# Sheet2.net
KiCad netlist of a schematic drawn in Altium Designer
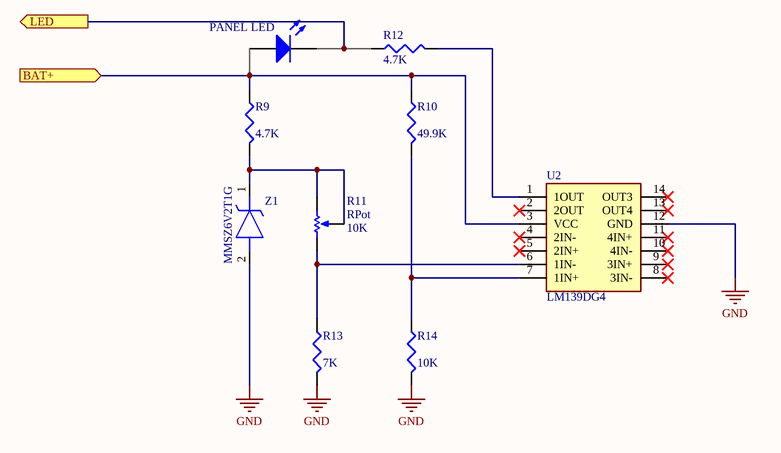
[diagram p0: Sheet2.SchDoc]

(export (version "E")
  (design (tool "Eeschema 10.0.6"))
  (components
    (comp (ref "D5")
      (value "PANEL LED")
      (footprint "LED-1")
      (description "Typical BLUE SiC LED")
      (fields (field (name "PUBLISHER") "Altium Limited"))
      (libsource (lib "Miscellaneous Devices") (part "LED3"))
    )
    (comp (ref "R9")
      (value "4.7K")
      (footprint "RESC1608X55N")
      (description "Resistor")
      (fields (field (name "Comment") "Res3") (field (name "PUBLISHER") "Altium Limited"))
      (libsource (lib "Miscellaneous Devices") (part "Res3"))
    )
    (comp (ref "R10")
      (value "49.9K")
      (footprint "RESC1608X55N")
      (description "Resistor")
      (fields (field (name "Comment") "Res3") (field (name "PUBLISHER") "Altium Limited"))
      (libsource (lib "Miscellaneous Devices") (part "Res3"))
    )
    (comp (ref "R11")
      (value "RPot")
      (footprint "Bourns_Pot")
      (description "Potentiometer")
      (fields (field (name "ALTIUM_VALUE") "10K") (field (name "PUBLISHER") "Altium Limited"))
      (libsource (lib "Miscellaneous Devices") (part "RPot"))
    )
    (comp (ref "R12")
      (value "4.7K")
      (footprint "RESC1608X55N")
      (description "Resistor")
      (fields (field (name "Comment") "Res3") (field (name "PUBLISHER") "Altium Limited"))
      (libsource (lib "Miscellaneous Devices") (part "Res3"))
    )
    (comp (ref "R13")
      (value "7K")
      (footprint "RESC1608X55N")
      (description "Resistor")
      (fields (field (name "Comment") "Res3") (field (name "PUBLISHER") "Altium Limited"))
      (libsource (lib "Miscellaneous Devices") (part "Res3"))
    )
    (comp (ref "R14")
      (value "10K")
      (footprint "RESC1608X55N")
      (description "Resistor")
      (fields (field (name "Comment") "Res3") (field (name "PUBLISHER") "Altium Limited"))
      (libsource (lib "Miscellaneous Devices") (part "Res3"))
    )
    (comp (ref "U2")
      (value "LM139DG4")
      (footprint "SamacSys:SOIC127P600X175-14N")
      (description "Integrated Circuit")
      (fields (field (name "MOUSER PART NUMBER") "595-LM139DG4"))
      (libsource (lib "*") (part "LM139DG4"))
    )
    (comp (ref "Z1")
      (value "MMSZ6V2T1G")
      (footprint "SamacSys:SOD3716X135N")
      (description "Zener Diode")
      (fields (field (name "MOUSER PART NUMBER") "863-MMSZ6V2T1G"))
      (libsource (lib "*") (part "MMSZ6V2T1G"))
    )
  )
  (nets
    (net (code "1") (name "/BAT+") (class "Default")
      (node (ref "D5") (pin "1") (pinfunction "A_1") (pintype "passive"))
      (node (ref "R10") (pin "1") (pinfunction "1_1") (pintype "passive"))
      (node (ref "R9") (pin "1") (pinfunction "1_1") (pintype "passive"))
      (node (ref "U2") (pin "3") (pinfunction "VCC_3") (pintype "passive"))
    )
    (net (code "2") (name "/LED") (class "Default")
      (node (ref "D5") (pin "2") (pinfunction "K_2") (pintype "passive"))
      (node (ref "R12") (pin "1") (pinfunction "1_1") (pintype "passive"))
    )
    (net (code "3") (name "GND") (class "Default")
      (node (ref "R13") (pin "2") (pinfunction "2_2") (pintype "passive"))
      (node (ref "R14") (pin "2") (pinfunction "2_2") (pintype "passive"))
      (node (ref "U2") (pin "12") (pinfunction "GND_12") (pintype "passive"))
      (node (ref "Z1") (pin "2") (pinfunction "A_2") (pintype "passive"))
    )
    (net (code "4") (name "Net-(R11-BOT)") (class "Default")
      (node (ref "R11") (pin "2") (pinfunction "BOT_2") (pintype "passive"))
      (node (ref "R11") (pin "3") (pinfunction "TAP_3") (pintype "passive"))
      (node (ref "R9") (pin "2") (pinfunction "2_2") (pintype "passive"))
      (node (ref "Z1") (pin "1") (pinfunction "K_1") (pintype "passive"))
    )
    (net (code "5") (name "Net-(R11-TOP)") (class "Default")
      (node (ref "R11") (pin "1") (pinfunction "TOP_1") (pintype "passive"))
      (node (ref "R13") (pin "1") (pinfunction "1_1") (pintype "passive"))
      (node (ref "U2") (pin "6") (pinfunction "1IN-_6") (pintype "passive"))
    )
    (net (code "6") (name "Net-(U2-1IN+)") (class "Default")
      (node (ref "R10") (pin "2") (pinfunction "2_2") (pintype "passive"))
      (node (ref "R14") (pin "1") (pinfunction "1_1") (pintype "passive"))
      (node (ref "U2") (pin "7") (pinfunction "1IN+_7") (pintype "passive"))
    )
    (net (code "7") (name "Net-(U2-1OUT)") (class "Default")
      (node (ref "R12") (pin "2") (pinfunction "2_2") (pintype "passive"))
      (node (ref "U2") (pin "1") (pinfunction "1OUT_1") (pintype "passive"))
    )
    (net (code "8") (name "unconnected-(U2-2IN+-Pad5)") (class "Default")
      (node (ref "U2") (pin "5") (pinfunction "2IN+_5") (pintype "passive+no_connect"))
    )
    (net (code "9") (name "unconnected-(U2-2IN--Pad4)") (class "Default")
      (node (ref "U2") (pin "4") (pinfunction "2IN-_4") (pintype "passive+no_connect"))
    )
    (net (code "10") (name "unconnected-(U2-2OUT-Pad2)") (class "Default")
      (node (ref "U2") (pin "2") (pinfunction "2OUT_2") (pintype "passive+no_connect"))
    )
    (net (code "11") (name "unconnected-(U2-3IN+-Pad9)") (class "Default")
      (node (ref "U2") (pin "9") (pinfunction "3IN+_9") (pintype "passive+no_connect"))
    )
    (net (code "12") (name "unconnected-(U2-3IN--Pad8)") (class "Default")
      (node (ref "U2") (pin "8") (pinfunction "3IN-_8") (pintype "passive+no_connect"))
    )
    (net (code "13") (name "unconnected-(U2-4IN+-Pad11)") (class "Default")
      (node (ref "U2") (pin "11") (pinfunction "4IN+_11") (pintype "passive+no_connect"))
    )
    (net (code "14") (name "unconnected-(U2-4IN--Pad10)") (class "Default")
      (node (ref "U2") (pin "10") (pinfunction "4IN-_10") (pintype "passive+no_connect"))
    )
    (net (code "15") (name "unconnected-(U2-OUT3-Pad14)") (class "Default")
      (node (ref "U2") (pin "14") (pinfunction "OUT3_14") (pintype "passive+no_connect"))
    )
    (net (code "16") (name "unconnected-(U2-OUT4-Pad13)") (class "Default")
      (node (ref "U2") (pin "13") (pinfunction "OUT4_13") (pintype "passive+no_connect"))
    )
  )
)
